# AJAPixel.net
KiCad netlist of a schematic drawn in EAGLE
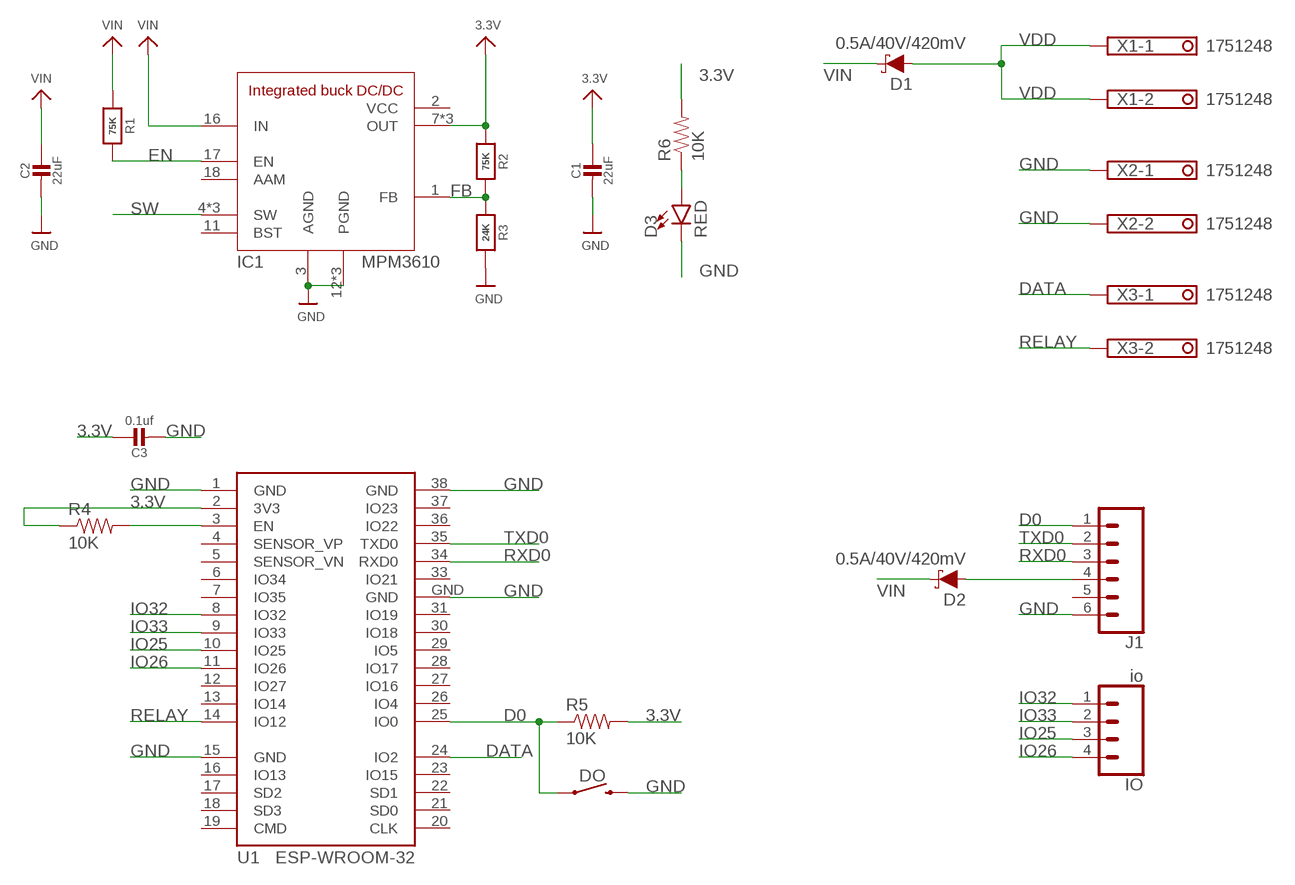
[diagram p0: schematic, sheet 1]

(export (version "E")
  (design (tool "Eeschema 10.0.6"))
  (components
    (comp (ref "C1")
      (value "22uF")
      (footprint "eagle-import:0805-NO")
      (libsource (lib "eagle-import") (part "microbuilder_CAP_CERAMIC0805-NOOUTLINE"))
    )
    (comp (ref "C2")
      (value "22uF")
      (footprint "eagle-import:0805-NO")
      (libsource (lib "eagle-import") (part "microbuilder_CAP_CERAMIC0805-NOOUTLINE"))
    )
    (comp (ref "C3")
      (value "0.1uf")
      (footprint "eagle-import:_0603")
      (libsource (lib "eagle-import") (part "CAP_CERAMIC_0603"))
    )
    (comp (ref "D1")
      (value "0.5A/40V/420mV")
      (footprint "eagle-import:SOD-323")
      (libsource (lib "eagle-import") (part "DIODE-SCHOTTKY-PMEG4005EJ"))
    )
    (comp (ref "D2")
      (value "0.5A/40V/420mV")
      (footprint "eagle-import:SOD-323")
      (libsource (lib "eagle-import") (part "DIODE-SCHOTTKY-PMEG4005EJ"))
    )
    (comp (ref "D3")
      (value "RED")
      (footprint "eagle-import:LED-0603")
      (libsource (lib "eagle-import") (part "LED-RED0603"))
    )
    (comp (ref "DO")
      (value "MOMENTARY-SWITCH-SPST-SMD-5.2MM")
      (footprint "eagle-import:TACTILE_SWITCH_SMD_5.2MM")
      (libsource (lib "eagle-import") (part "MOMENTARY-SWITCH-SPST-SMD-5.2MM"))
    )
    (comp (ref "IC1")
      (value "MPM3610")
      (footprint "eagle-import:MPM3610")
      (libsource (lib "eagle-import") (part "MPM3610"))
    )
    (comp (ref "IO")
      (value "io")
      (footprint "eagle-import:1X04")
      (libsource (lib "eagle-import") (part "CONN_04"))
    )
    (comp (ref "J1")
      (value "CONN_06SILK_FEMALE_PTH")
      (footprint "eagle-import:1X06")
      (libsource (lib "eagle-import") (part "CONN_06SILK_FEMALE_PTH"))
    )
    (comp (ref "R1")
      (value "75K")
      (footprint "eagle-import:0603-NO")
      (libsource (lib "eagle-import") (part "RESISTOR_0603_NOOUT"))
    )
    (comp (ref "R2")
      (value "75K")
      (footprint "eagle-import:0603-NO")
      (libsource (lib "eagle-import") (part "RESISTOR_0603_NOOUT"))
    )
    (comp (ref "R3")
      (value "24K")
      (footprint "eagle-import:0603-NO")
      (libsource (lib "eagle-import") (part "RESISTOR_0603_NOOUT"))
    )
    (comp (ref "R4")
      (value "10K")
      (footprint "eagle-import:0603")
      (libsource (lib "eagle-import") (part "27OHM1/10W1%(0603)"))
    )
    (comp (ref "R5")
      (value "10K")
      (footprint "eagle-import:0603")
      (libsource (lib "eagle-import") (part "27OHM1/10W1%(0603)"))
    )
    (comp (ref "R6")
      (value "10K")
      (footprint "eagle-import:0603")
      (libsource (lib "eagle-import") (part "27OHM1/10W1%(0603)"))
    )
    (comp (ref "U1")
      (value "ESP-WROOM-32")
      (footprint "eagle-import:ESP-WROOM-32")
      (libsource (lib "eagle-import") (part "ESP-WROOM-32"))
    )
    (comp (ref "X1")
      (value "1751248")
      (footprint "eagle-import:1751248")
      (libsource (lib "eagle-import") (part "1751248"))
    )
    (comp (ref "X2")
      (value "1751248")
      (footprint "eagle-import:1751248")
      (libsource (lib "eagle-import") (part "1751248"))
    )
    (comp (ref "X3")
      (value "1751248")
      (footprint "eagle-import:1751248")
      (libsource (lib "eagle-import") (part "1751248"))
    )
  )
  (nets
    (net (code "1") (name "/D0") (class "Default")
      (node (ref "DO") (pin "1") (pinfunction "1_1") (pintype "passive"))
      (node (ref "J1") (pin "1") (pinfunction "1_1") (pintype "passive"))
      (node (ref "R5") (pin "1") (pinfunction "1_1") (pintype "passive"))
      (node (ref "U1") (pin "25") (pinfunction "IO0_25") (pintype "bidirectional"))
    )
    (net (code "2") (name "/DATA") (class "Default")
      (node (ref "U1") (pin "24") (pinfunction "IO2_24") (pintype "bidirectional"))
      (node (ref "X3") (pin "1") (pinfunction "K_1") (pintype "passive"))
    )
    (net (code "3") (name "/EN") (class "Default")
      (node (ref "IC1") (pin "17") (pinfunction "EN_17") (pintype "input"))
      (node (ref "R1") (pin "2") (pinfunction "2_2") (pintype "passive"))
    )
    (net (code "4") (name "/FB") (class "Default")
      (node (ref "IC1") (pin "1") (pinfunction "FB_1") (pintype "input"))
      (node (ref "R2") (pin "2") (pinfunction "2_2") (pintype "passive"))
      (node (ref "R3") (pin "1") (pinfunction "1_1") (pintype "passive"))
    )
    (net (code "5") (name "/IO25") (class "Default")
      (node (ref "IO") (pin "3") (pinfunction "3_3") (pintype "passive"))
      (node (ref "U1") (pin "10") (pinfunction "IO25_10") (pintype "bidirectional"))
    )
    (net (code "6") (name "/IO26") (class "Default")
      (node (ref "IO") (pin "4") (pinfunction "4_4") (pintype "passive"))
      (node (ref "U1") (pin "11") (pinfunction "IO26_11") (pintype "bidirectional"))
    )
    (net (code "7") (name "/IO32") (class "Default")
      (node (ref "IO") (pin "1") (pinfunction "1_1") (pintype "passive"))
      (node (ref "U1") (pin "8") (pinfunction "IO32_8") (pintype "bidirectional"))
    )
    (net (code "8") (name "/IO33") (class "Default")
      (node (ref "IO") (pin "2") (pinfunction "2_2") (pintype "passive"))
      (node (ref "U1") (pin "9") (pinfunction "IO33_9") (pintype "bidirectional"))
    )
    (net (code "9") (name "/RELAY") (class "Default")
      (node (ref "U1") (pin "14") (pinfunction "IO12_14") (pintype "bidirectional"))
      (node (ref "X3") (pin "2") (pinfunction "K_2") (pintype "passive"))
    )
    (net (code "10") (name "/RXD0") (class "Default")
      (node (ref "J1") (pin "3") (pinfunction "3_3") (pintype "passive"))
      (node (ref "U1") (pin "34") (pinfunction "RXD0_34") (pintype "bidirectional"))
    )
    (net (code "11") (name "/SW") (class "Default")
      (node (ref "IC1") (pin "4") (pinfunction "SW_4") (pintype "passive"))
      (node (ref "IC1") (pin "5") (pinfunction "SW_5") (pintype "passive"))
      (node (ref "IC1") (pin "6") (pinfunction "SW_6") (pintype "passive"))
    )
    (net (code "12") (name "/TXD0") (class "Default")
      (node (ref "J1") (pin "2") (pinfunction "2_2") (pintype "passive"))
      (node (ref "U1") (pin "35") (pinfunction "TXD0_35") (pintype "bidirectional"))
    )
    (net (code "13") (name "/VCC") (class "Default")
      (node (ref "IC1") (pin "2") (pinfunction "VCC_2") (pintype "power_in"))
    )
    (net (code "14") (name "/VDD") (class "Default")
      (node (ref "D1") (pin "A") (pinfunction "A_A") (pintype "passive"))
      (node (ref "X1") (pin "1") (pinfunction "K_1") (pintype "passive"))
      (node (ref "X1") (pin "2") (pinfunction "K_2") (pintype "passive"))
    )
    (net (code "15") (name "3.3V") (class "Default")
      (node (ref "C1") (pin "1") (pinfunction "1_1") (pintype "passive"))
      (node (ref "C3") (pin "1") (pinfunction "1_1") (pintype "passive"))
      (node (ref "IC1") (pin "7") (pinfunction "OUT_7") (pintype "power_in"))
      (node (ref "IC1") (pin "8") (pinfunction "OUT_8") (pintype "power_in"))
      (node (ref "IC1") (pin "9") (pinfunction "OUT_9") (pintype "power_in"))
      (node (ref "R2") (pin "1") (pinfunction "1_1") (pintype "passive"))
      (node (ref "R4") (pin "1") (pinfunction "1_1") (pintype "passive"))
      (node (ref "R5") (pin "2") (pinfunction "2_2") (pintype "passive"))
      (node (ref "R6") (pin "2") (pinfunction "2_2") (pintype "passive"))
      (node (ref "U1") (pin "2") (pinfunction "3V3_2") (pintype "power_in"))
    )
    (net (code "16") (name "GND") (class "Default")
      (node (ref "C1") (pin "2") (pinfunction "2_2") (pintype "passive"))
      (node (ref "C2") (pin "2") (pinfunction "2_2") (pintype "passive"))
      (node (ref "C3") (pin "2") (pinfunction "2_2") (pintype "passive"))
      (node (ref "D3") (pin "C") (pinfunction "C_C") (pintype "passive"))
      (node (ref "DO") (pin "3") (pinfunction "2_3") (pintype "passive"))
      (node (ref "IC1") (pin "12") (pinfunction "PGND_12") (pintype "power_in"))
      (node (ref "IC1") (pin "13") (pinfunction "PGND_13") (pintype "power_in"))
      (node (ref "IC1") (pin "14") (pinfunction "PGND_14") (pintype "power_in"))
      (node (ref "IC1") (pin "3") (pinfunction "AGND_3") (pintype "power_in"))
      (node (ref "J1") (pin "6") (pinfunction "6_6") (pintype "passive"))
      (node (ref "R3") (pin "2") (pinfunction "2_2") (pintype "passive"))
      (node (ref "U1") (pin "1") (pinfunction "GND_1") (pintype "power_in"))
      (node (ref "U1") (pin "15") (pinfunction "GND_15") (pintype "power_in"))
      (node (ref "U1") (pin "38") (pinfunction "GND_38") (pintype "power_in"))
      (node (ref "U1") (pin "GND") (pinfunction "GND_GND") (pintype "power_in"))
      (node (ref "X2") (pin "1") (pinfunction "K_1") (pintype "passive"))
      (node (ref "X2") (pin "2") (pinfunction "K_2") (pintype "passive"))
    )
    (net (code "17") (name "Net-(D2-PadA)") (class "Default")
      (node (ref "D2") (pin "A") (pinfunction "A_A") (pintype "passive"))
      (node (ref "J1") (pin "4") (pinfunction "4_4") (pintype "passive"))
    )
    (net (code "18") (name "Net-(D3-PadA)") (class "Default")
      (node (ref "D3") (pin "A") (pinfunction "A_A") (pintype "passive"))
      (node (ref "R6") (pin "1") (pinfunction "1_1") (pintype "passive"))
    )
    (net (code "19") (name "Net-(U1-EN)") (class "Default")
      (node (ref "R4") (pin "2") (pinfunction "2_2") (pintype "passive"))
      (node (ref "U1") (pin "3") (pinfunction "EN_3") (pintype "input"))
    )
    (net (code "20") (name "VIN") (class "Default")
      (node (ref "C2") (pin "1") (pinfunction "1_1") (pintype "passive"))
      (node (ref "D1") (pin "C") (pinfunction "C_C") (pintype "passive"))
      (node (ref "D2") (pin "C") (pinfunction "C_C") (pintype "passive"))
      (node (ref "IC1") (pin "16") (pinfunction "IN_16") (pintype "power_in"))
      (node (ref "R1") (pin "1") (pinfunction "1_1") (pintype "passive"))
    )
    (net (code "21") (name "unconnected-(IC1-AAM-Pad18)") (class "Default")
      (node (ref "IC1") (pin "18") (pinfunction "AAM_18") (pintype "input"))
    )
    (net (code "22") (name "unconnected-(IC1-BST-Pad11)") (class "Default")
      (node (ref "IC1") (pin "11") (pinfunction "BST_11") (pintype "passive"))
    )
    (net (code "23") (name "unconnected-(J1-Pad5)") (class "Default")
      (node (ref "J1") (pin "5") (pinfunction "5_5") (pintype "passive"))
    )
    (net (code "24") (name "unconnected-(U1-CLK-Pad20)") (class "Default")
      (node (ref "U1") (pin "20") (pinfunction "CLK_20") (pintype "bidirectional"))
    )
    (net (code "25") (name "unconnected-(U1-CMD-Pad19)") (class "Default")
      (node (ref "U1") (pin "19") (pinfunction "CMD_19") (pintype "bidirectional"))
    )
    (net (code "26") (name "unconnected-(U1-IO4-Pad26)") (class "Default")
      (node (ref "U1") (pin "26") (pinfunction "IO4_26") (pintype "bidirectional"))
    )
    (net (code "27") (name "unconnected-(U1-IO5-Pad29)") (class "Default")
      (node (ref "U1") (pin "29") (pinfunction "IO5_29") (pintype "bidirectional"))
    )
    (net (code "28") (name "unconnected-(U1-IO13-Pad16)") (class "Default")
      (node (ref "U1") (pin "16") (pinfunction "IO13_16") (pintype "bidirectional"))
    )
    (net (code "29") (name "unconnected-(U1-IO14-Pad13)") (class "Default")
      (node (ref "U1") (pin "13") (pinfunction "IO14_13") (pintype "bidirectional"))
    )
    (net (code "30") (name "unconnected-(U1-IO15-Pad23)") (class "Default")
      (node (ref "U1") (pin "23") (pinfunction "IO15_23") (pintype "bidirectional"))
    )
    (net (code "31") (name "unconnected-(U1-IO16-Pad27)") (class "Default")
      (node (ref "U1") (pin "27") (pinfunction "IO16_27") (pintype "bidirectional"))
    )
    (net (code "32") (name "unconnected-(U1-IO17-Pad28)") (class "Default")
      (node (ref "U1") (pin "28") (pinfunction "IO17_28") (pintype "bidirectional"))
    )
    (net (code "33") (name "unconnected-(U1-IO18-Pad30)") (class "Default")
      (node (ref "U1") (pin "30") (pinfunction "IO18_30") (pintype "bidirectional"))
    )
    (net (code "34") (name "unconnected-(U1-IO19-Pad31)") (class "Default")
      (node (ref "U1") (pin "31") (pinfunction "IO19_31") (pintype "bidirectional"))
    )
    (net (code "35") (name "unconnected-(U1-IO21-Pad33)") (class "Default")
      (node (ref "U1") (pin "33") (pinfunction "IO21_33") (pintype "bidirectional"))
    )
    (net (code "36") (name "unconnected-(U1-IO22-Pad36)") (class "Default")
      (node (ref "U1") (pin "36") (pinfunction "IO22_36") (pintype "bidirectional"))
    )
    (net (code "37") (name "unconnected-(U1-IO23-Pad37)") (class "Default")
      (node (ref "U1") (pin "37") (pinfunction "IO23_37") (pintype "bidirectional"))
    )
    (net (code "38") (name "unconnected-(U1-IO27-Pad12)") (class "Default")
      (node (ref "U1") (pin "12") (pinfunction "IO27_12") (pintype "bidirectional"))
    )
    (net (code "39") (name "unconnected-(U1-IO34-Pad6)") (class "Default")
      (node (ref "U1") (pin "6") (pinfunction "IO34_6") (pintype "bidirectional"))
    )
    (net (code "40") (name "unconnected-(U1-IO35-Pad7)") (class "Default")
      (node (ref "U1") (pin "7") (pinfunction "IO35_7") (pintype "bidirectional"))
    )
    (net (code "41") (name "unconnected-(U1-SD0-Pad21)") (class "Default")
      (node (ref "U1") (pin "21") (pinfunction "SD0_21") (pintype "bidirectional"))
    )
    (net (code "42") (name "unconnected-(U1-SD1-Pad22)") (class "Default")
      (node (ref "U1") (pin "22") (pinfunction "SD1_22") (pintype "bidirectional"))
    )
    (net (code "43") (name "unconnected-(U1-SD2-Pad17)") (class "Default")
      (node (ref "U1") (pin "17") (pinfunction "SD2_17") (pintype "bidirectional"))
    )
    (net (code "44") (name "unconnected-(U1-SD3-Pad18)") (class "Default")
      (node (ref "U1") (pin "18") (pinfunction "SD3_18") (pintype "bidirectional"))
    )
    (net (code "45") (name "unconnected-(U1-SENSOR_VN-Pad5)") (class "Default")
      (node (ref "U1") (pin "5") (pinfunction "SENSOR_VN_5") (pintype "bidirectional"))
    )
    (net (code "46") (name "unconnected-(U1-SENSOR_VP-Pad4)") (class "Default")
      (node (ref "U1") (pin "4") (pinfunction "SENSOR_VP_4") (pintype "bidirectional"))
    )
  )
)
